# flyback.net
KiCad netlist of a schematic drawn in EAGLE
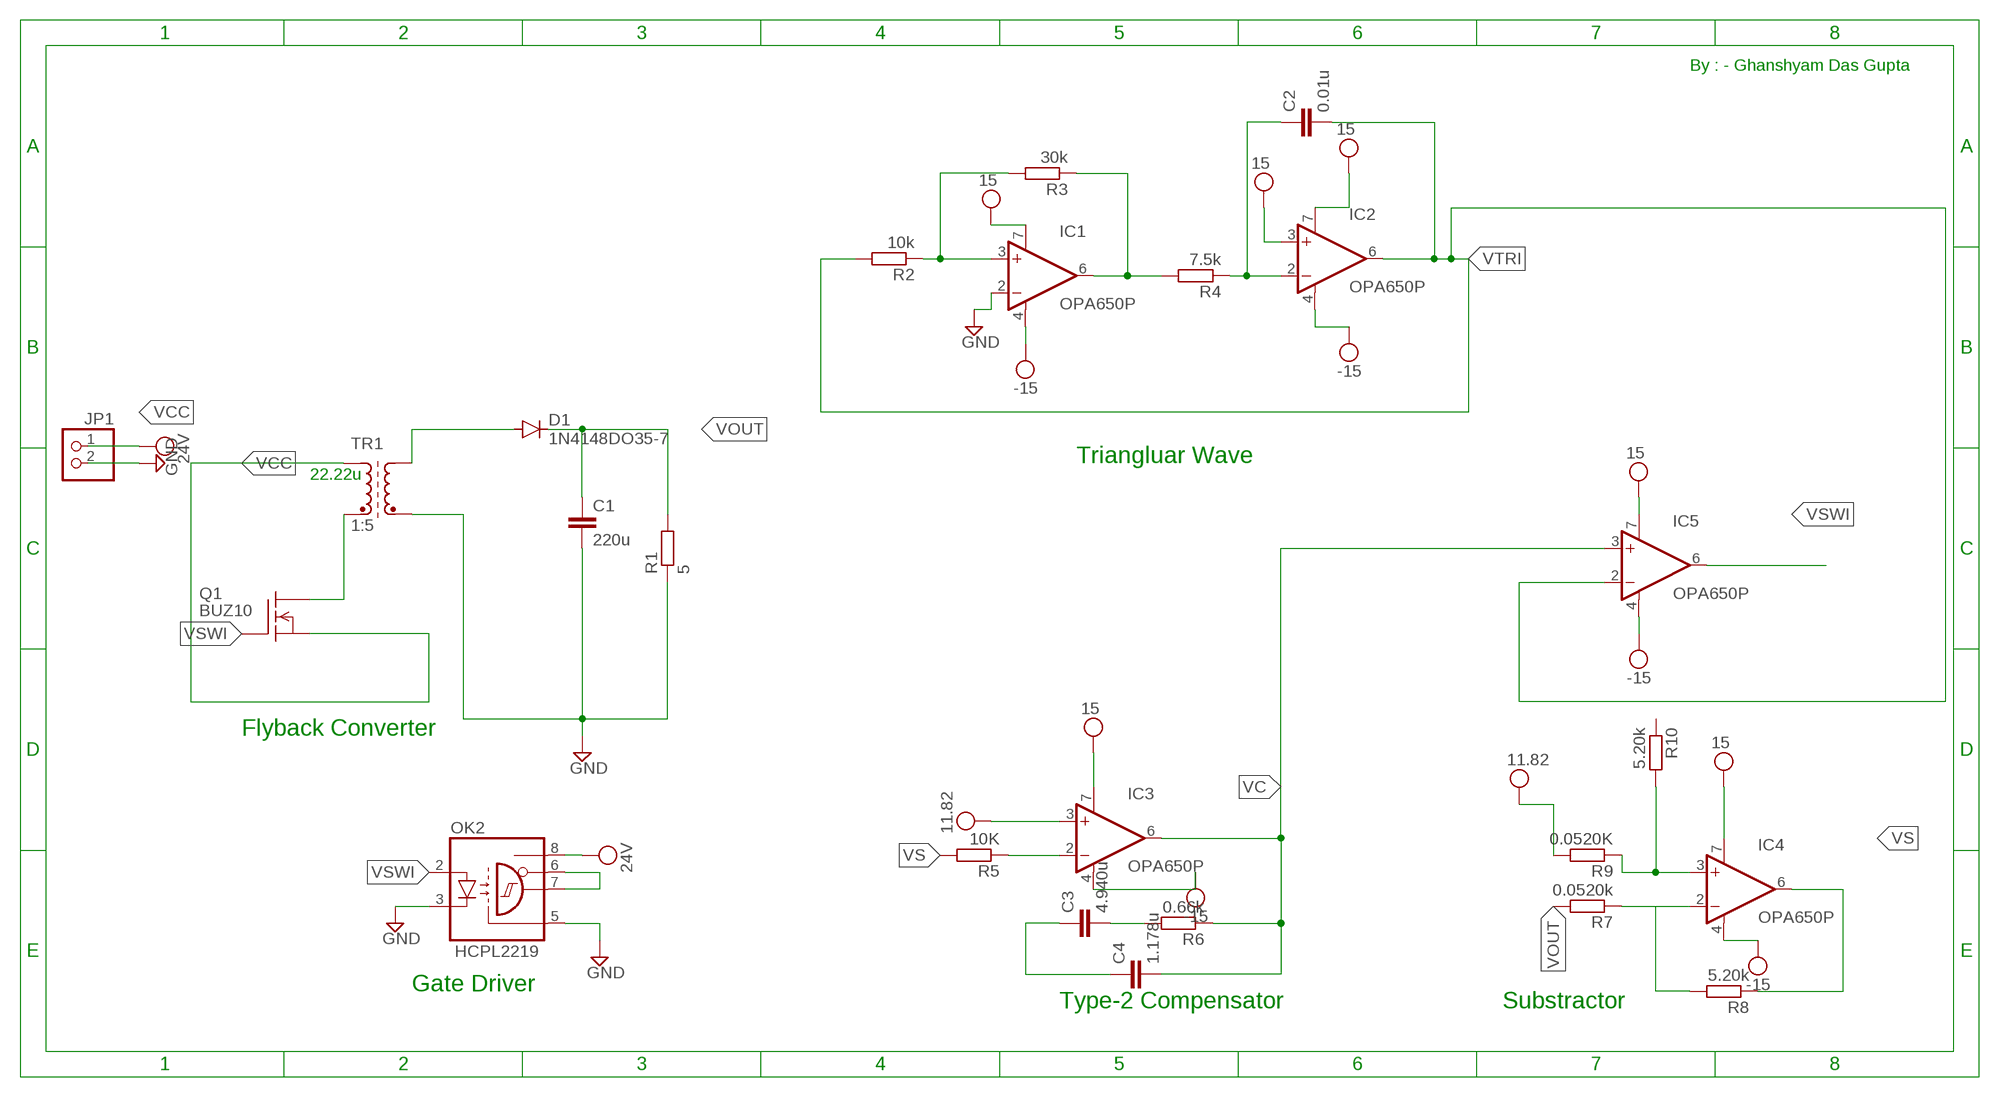
[diagram p0: schematic, sheet 1]

(export (version "E")
  (design (tool "Eeschema 10.0.6"))
  (components
    (comp (ref "C1")
      (value "220u")
      (footprint "eagle-import:C050-050X075")
      (libsource (lib "eagle-import") (part "C-EU050-050X075"))
    )
    (comp (ref "C2")
      (value "0.01u")
      (footprint "eagle-import:C050-050X075")
      (libsource (lib "eagle-import") (part "C-EU050-050X075"))
    )
    (comp (ref "C3")
      (value "4.940u")
      (footprint "eagle-import:C050-050X075")
      (libsource (lib "eagle-import") (part "C-EU050-050X075"))
    )
    (comp (ref "C4")
      (value "1.178u")
      (footprint "eagle-import:C050-050X075")
      (libsource (lib "eagle-import") (part "C-EU050-050X075"))
    )
    (comp (ref "D1")
      (value "1N4148DO35-7")
      (footprint "eagle-import:DO35-7")
      (libsource (lib "eagle-import") (part "1N4148DO35-7"))
    )
    (comp (ref "IC1")
      (value "OPA650P")
      (footprint "eagle-import:DIL08")
      (libsource (lib "eagle-import") (part "OPA650P"))
    )
    (comp (ref "IC2")
      (value "OPA650P")
      (footprint "eagle-import:DIL08")
      (libsource (lib "eagle-import") (part "OPA650P"))
    )
    (comp (ref "IC3")
      (value "OPA650P")
      (footprint "eagle-import:DIL08")
      (libsource (lib "eagle-import") (part "OPA650P"))
    )
    (comp (ref "IC4")
      (value "OPA650P")
      (footprint "eagle-import:DIL08")
      (libsource (lib "eagle-import") (part "OPA650P"))
    )
    (comp (ref "IC5")
      (value "OPA650P")
      (footprint "eagle-import:DIL08")
      (libsource (lib "eagle-import") (part "OPA650P"))
    )
    (comp (ref "JP1")
      (value "PINHD-1X2")
      (footprint "eagle-import:1X02")
      (libsource (lib "eagle-import") (part "PINHD-1X2"))
    )
    (comp (ref "OK2")
      (value "HCPL2219")
      (footprint "eagle-import:DIL08")
      (fields (field (name "MF") "AGILENT TECHNOLOGIES") (field (name "MPN") "HCPL-2219-000E"))
      (libsource (lib "eagle-import") (part "HCPL2219"))
    )
    (comp (ref "Q1")
      (value "BUZ10")
      (footprint "eagle-import:TO220")
      (libsource (lib "eagle-import") (part "BUZ10"))
    )
    (comp (ref "R1")
      (value "5")
      (footprint "eagle-import:0414_15")
      (libsource (lib "eagle-import") (part "R-EU_0414/15"))
    )
    (comp (ref "R2")
      (value "10k")
      (footprint "eagle-import:0414_15")
      (libsource (lib "eagle-import") (part "R-EU_0414/15"))
    )
    (comp (ref "R3")
      (value "30k")
      (footprint "eagle-import:0414_15")
      (libsource (lib "eagle-import") (part "R-EU_0414/15"))
    )
    (comp (ref "R4")
      (value "7.5k")
      (footprint "eagle-import:0414_15")
      (libsource (lib "eagle-import") (part "R-EU_0414/15"))
    )
    (comp (ref "R5")
      (value "10K")
      (footprint "eagle-import:0414_15")
      (libsource (lib "eagle-import") (part "R-EU_0414/15"))
    )
    (comp (ref "R6")
      (value "0.66k")
      (footprint "eagle-import:0414_15")
      (libsource (lib "eagle-import") (part "R-EU_0414/15"))
    )
    (comp (ref "R7")
      (value "0.0520k")
      (footprint "eagle-import:0414_15")
      (libsource (lib "eagle-import") (part "R-EU_0414/15"))
    )
    (comp (ref "R8")
      (value "5.20k")
      (footprint "eagle-import:0414_15")
      (libsource (lib "eagle-import") (part "R-EU_0414/15"))
    )
    (comp (ref "R9")
      (value "0.0520K")
      (footprint "eagle-import:0414_15")
      (libsource (lib "eagle-import") (part "R-EU_0414/15"))
    )
    (comp (ref "R10")
      (value "5.20k")
      (footprint "eagle-import:0414_15")
      (libsource (lib "eagle-import") (part "R-EU_0414/15"))
    )
    (comp (ref "TR1")
      (value "1:5")
      (footprint "eagle-import:SM-T4")
      (libsource (lib "eagle-import") (part "SM-T4"))
    )
  )
  (nets
    (net (code "1") (name "GND") (class "Default")
      (node (ref "C1") (pin "2") (pinfunction "2_2") (pintype "passive"))
      (node (ref "IC1") (pin "2") (pinfunction "-IN_2") (pintype "input"))
      (node (ref "JP1") (pin "2") (pinfunction "2_2") (pintype "passive"))
      (node (ref "OK2") (pin "3") (pinfunction "C_3") (pintype "passive"))
      (node (ref "OK2") (pin "5") (pinfunction "GND_5") (pintype "passive"))
      (node (ref "R1") (pin "1") (pinfunction "1_1") (pintype "passive"))
      (node (ref "TR1") (pin "4") (pinfunction "E2_4") (pintype "passive"))
    )
    (net (code "2") (name "Net-(C3-Pad1)") (class "Default")
      (node (ref "C3") (pin "1") (pinfunction "1_1") (pintype "passive"))
      (node (ref "C4") (pin "1") (pinfunction "1_1") (pintype "passive"))
    )
    (net (code "3") (name "Net-(C3-Pad2)") (class "Default")
      (node (ref "C3") (pin "2") (pinfunction "2_2") (pintype "passive"))
      (node (ref "R6") (pin "2") (pinfunction "2_2") (pintype "passive"))
    )
    (net (code "4") (name "Net-(IC1-+IN)") (class "Default")
      (node (ref "IC1") (pin "3") (pinfunction "+IN_3") (pintype "input"))
      (node (ref "R2") (pin "1") (pinfunction "1_1") (pintype "passive"))
      (node (ref "R3") (pin "2") (pinfunction "2_2") (pintype "passive"))
    )
    (net (code "5") (name "Net-(IC1-OUT)") (class "Default")
      (node (ref "IC1") (pin "6") (pinfunction "OUT_6") (pintype "output"))
      (node (ref "R3") (pin "1") (pinfunction "1_1") (pintype "passive"))
      (node (ref "R4") (pin "2") (pinfunction "2_2") (pintype "passive"))
    )
    (net (code "6") (name "Net-(IC2--IN)") (class "Default")
      (node (ref "C2") (pin "1") (pinfunction "1_1") (pintype "passive"))
      (node (ref "IC2") (pin "2") (pinfunction "-IN_2") (pintype "input"))
      (node (ref "R4") (pin "1") (pinfunction "1_1") (pintype "passive"))
    )
    (net (code "7") (name "Net-(IC3--IN)") (class "Default")
      (node (ref "IC3") (pin "2") (pinfunction "-IN_2") (pintype "input"))
      (node (ref "R5") (pin "1") (pinfunction "1_1") (pintype "passive"))
    )
    (net (code "8") (name "Net-(IC4-+IN)") (class "Default")
      (node (ref "IC4") (pin "3") (pinfunction "+IN_3") (pintype "input"))
      (node (ref "R10") (pin "2") (pinfunction "2_2") (pintype "passive"))
      (node (ref "R9") (pin "1") (pinfunction "1_1") (pintype "passive"))
    )
    (net (code "9") (name "Net-(IC4--IN)") (class "Default")
      (node (ref "IC4") (pin "2") (pinfunction "-IN_2") (pintype "input"))
      (node (ref "R7") (pin "1") (pinfunction "1_1") (pintype "passive"))
      (node (ref "R8") (pin "2") (pinfunction "2_2") (pintype "passive"))
    )
    (net (code "10") (name "Net-(OK2-VE)") (class "Default")
      (node (ref "OK2") (pin "6") (pinfunction "VE_6") (pintype "passive"))
      (node (ref "OK2") (pin "7") (pinfunction "VO_7") (pintype "passive"))
    )
    (net (code "11") (name "Net-(Q1-D)") (class "Default")
      (node (ref "Q1") (pin "2") (pinfunction "D_2") (pintype "passive"))
      (node (ref "TR1") (pin "2") (pinfunction "E1_2") (pintype "passive"))
    )
    (net (code "12") (name "Net-(Q1-S)") (class "Default")
      (node (ref "Q1") (pin "3") (pinfunction "S_3") (pintype "passive"))
      (node (ref "TR1") (pin "1") (pinfunction "A1_1") (pintype "passive"))
    )
    (net (code "13") (name "Net-(TR1-A2)") (class "Default")
      (node (ref "D1") (pin "A") (pinfunction "A_A") (pintype "passive"))
      (node (ref "TR1") (pin "5") (pinfunction "A2_5") (pintype "passive"))
    )
    (net (code "14") (name "VC") (class "Default")
      (node (ref "C4") (pin "2") (pinfunction "2_2") (pintype "passive"))
      (node (ref "IC3") (pin "6") (pinfunction "OUT_6") (pintype "output"))
      (node (ref "IC5") (pin "3") (pinfunction "+IN_3") (pintype "input"))
      (node (ref "R6") (pin "1") (pinfunction "1_1") (pintype "passive"))
    )
    (net (code "15") (name "VCC") (class "Default")
      (node (ref "IC1") (pin "4") (pinfunction "V-_4") (pintype "power_in"))
      (node (ref "IC1") (pin "7") (pinfunction "V+_7") (pintype "power_in"))
      (node (ref "IC2") (pin "3") (pinfunction "+IN_3") (pintype "input"))
      (node (ref "IC2") (pin "4") (pinfunction "V-_4") (pintype "power_in"))
      (node (ref "IC2") (pin "7") (pinfunction "V+_7") (pintype "power_in"))
      (node (ref "IC3") (pin "3") (pinfunction "+IN_3") (pintype "input"))
      (node (ref "IC3") (pin "4") (pinfunction "V-_4") (pintype "power_in"))
      (node (ref "IC3") (pin "7") (pinfunction "V+_7") (pintype "power_in"))
      (node (ref "IC4") (pin "4") (pinfunction "V-_4") (pintype "power_in"))
      (node (ref "IC4") (pin "7") (pinfunction "V+_7") (pintype "power_in"))
      (node (ref "IC5") (pin "4") (pinfunction "V-_4") (pintype "power_in"))
      (node (ref "IC5") (pin "7") (pinfunction "V+_7") (pintype "power_in"))
      (node (ref "JP1") (pin "1") (pinfunction "1_1") (pintype "passive"))
      (node (ref "OK2") (pin "8") (pinfunction "VCC_8") (pintype "passive"))
      (node (ref "R9") (pin "2") (pinfunction "2_2") (pintype "passive"))
    )
    (net (code "16") (name "VOUT") (class "Default")
      (node (ref "C1") (pin "1") (pinfunction "1_1") (pintype "passive"))
      (node (ref "D1") (pin "C") (pinfunction "C_C") (pintype "passive"))
      (node (ref "R1") (pin "2") (pinfunction "2_2") (pintype "passive"))
    )
    (net (code "17") (name "VS") (class "Default")
      (node (ref "IC4") (pin "6") (pinfunction "OUT_6") (pintype "output"))
      (node (ref "R8") (pin "1") (pinfunction "1_1") (pintype "passive"))
    )
    (net (code "18") (name "VSWI") (class "Default")
      (node (ref "IC5") (pin "6") (pinfunction "OUT_6") (pintype "output"))
    )
    (net (code "19") (name "VTRI") (class "Default")
      (node (ref "C2") (pin "2") (pinfunction "2_2") (pintype "passive"))
      (node (ref "IC2") (pin "6") (pinfunction "OUT_6") (pintype "output"))
      (node (ref "IC5") (pin "2") (pinfunction "-IN_2") (pintype "input"))
      (node (ref "R2") (pin "2") (pinfunction "2_2") (pintype "passive"))
    )
    (net (code "20") (name "unconnected-(OK2-A-Pad2)") (class "Default")
      (node (ref "OK2") (pin "2") (pinfunction "A_2") (pintype "passive"))
    )
    (net (code "21") (name "unconnected-(Q1-G-Pad1)") (class "Default")
      (node (ref "Q1") (pin "1") (pinfunction "G_1") (pintype "passive"))
    )
    (net (code "22") (name "unconnected-(R5-Pad2)") (class "Default")
      (node (ref "R5") (pin "2") (pinfunction "2_2") (pintype "passive"))
    )
    (net (code "23") (name "unconnected-(R7-Pad2)") (class "Default")
      (node (ref "R7") (pin "2") (pinfunction "2_2") (pintype "passive"))
    )
    (net (code "24") (name "unconnected-(R10-Pad1)") (class "Default")
      (node (ref "R10") (pin "1") (pinfunction "1_1") (pintype "passive"))
    )
  )
)
